# SCH_strip-table_2023-05-29.net
KiCad netlist of a schematic drawn in EasyEDA
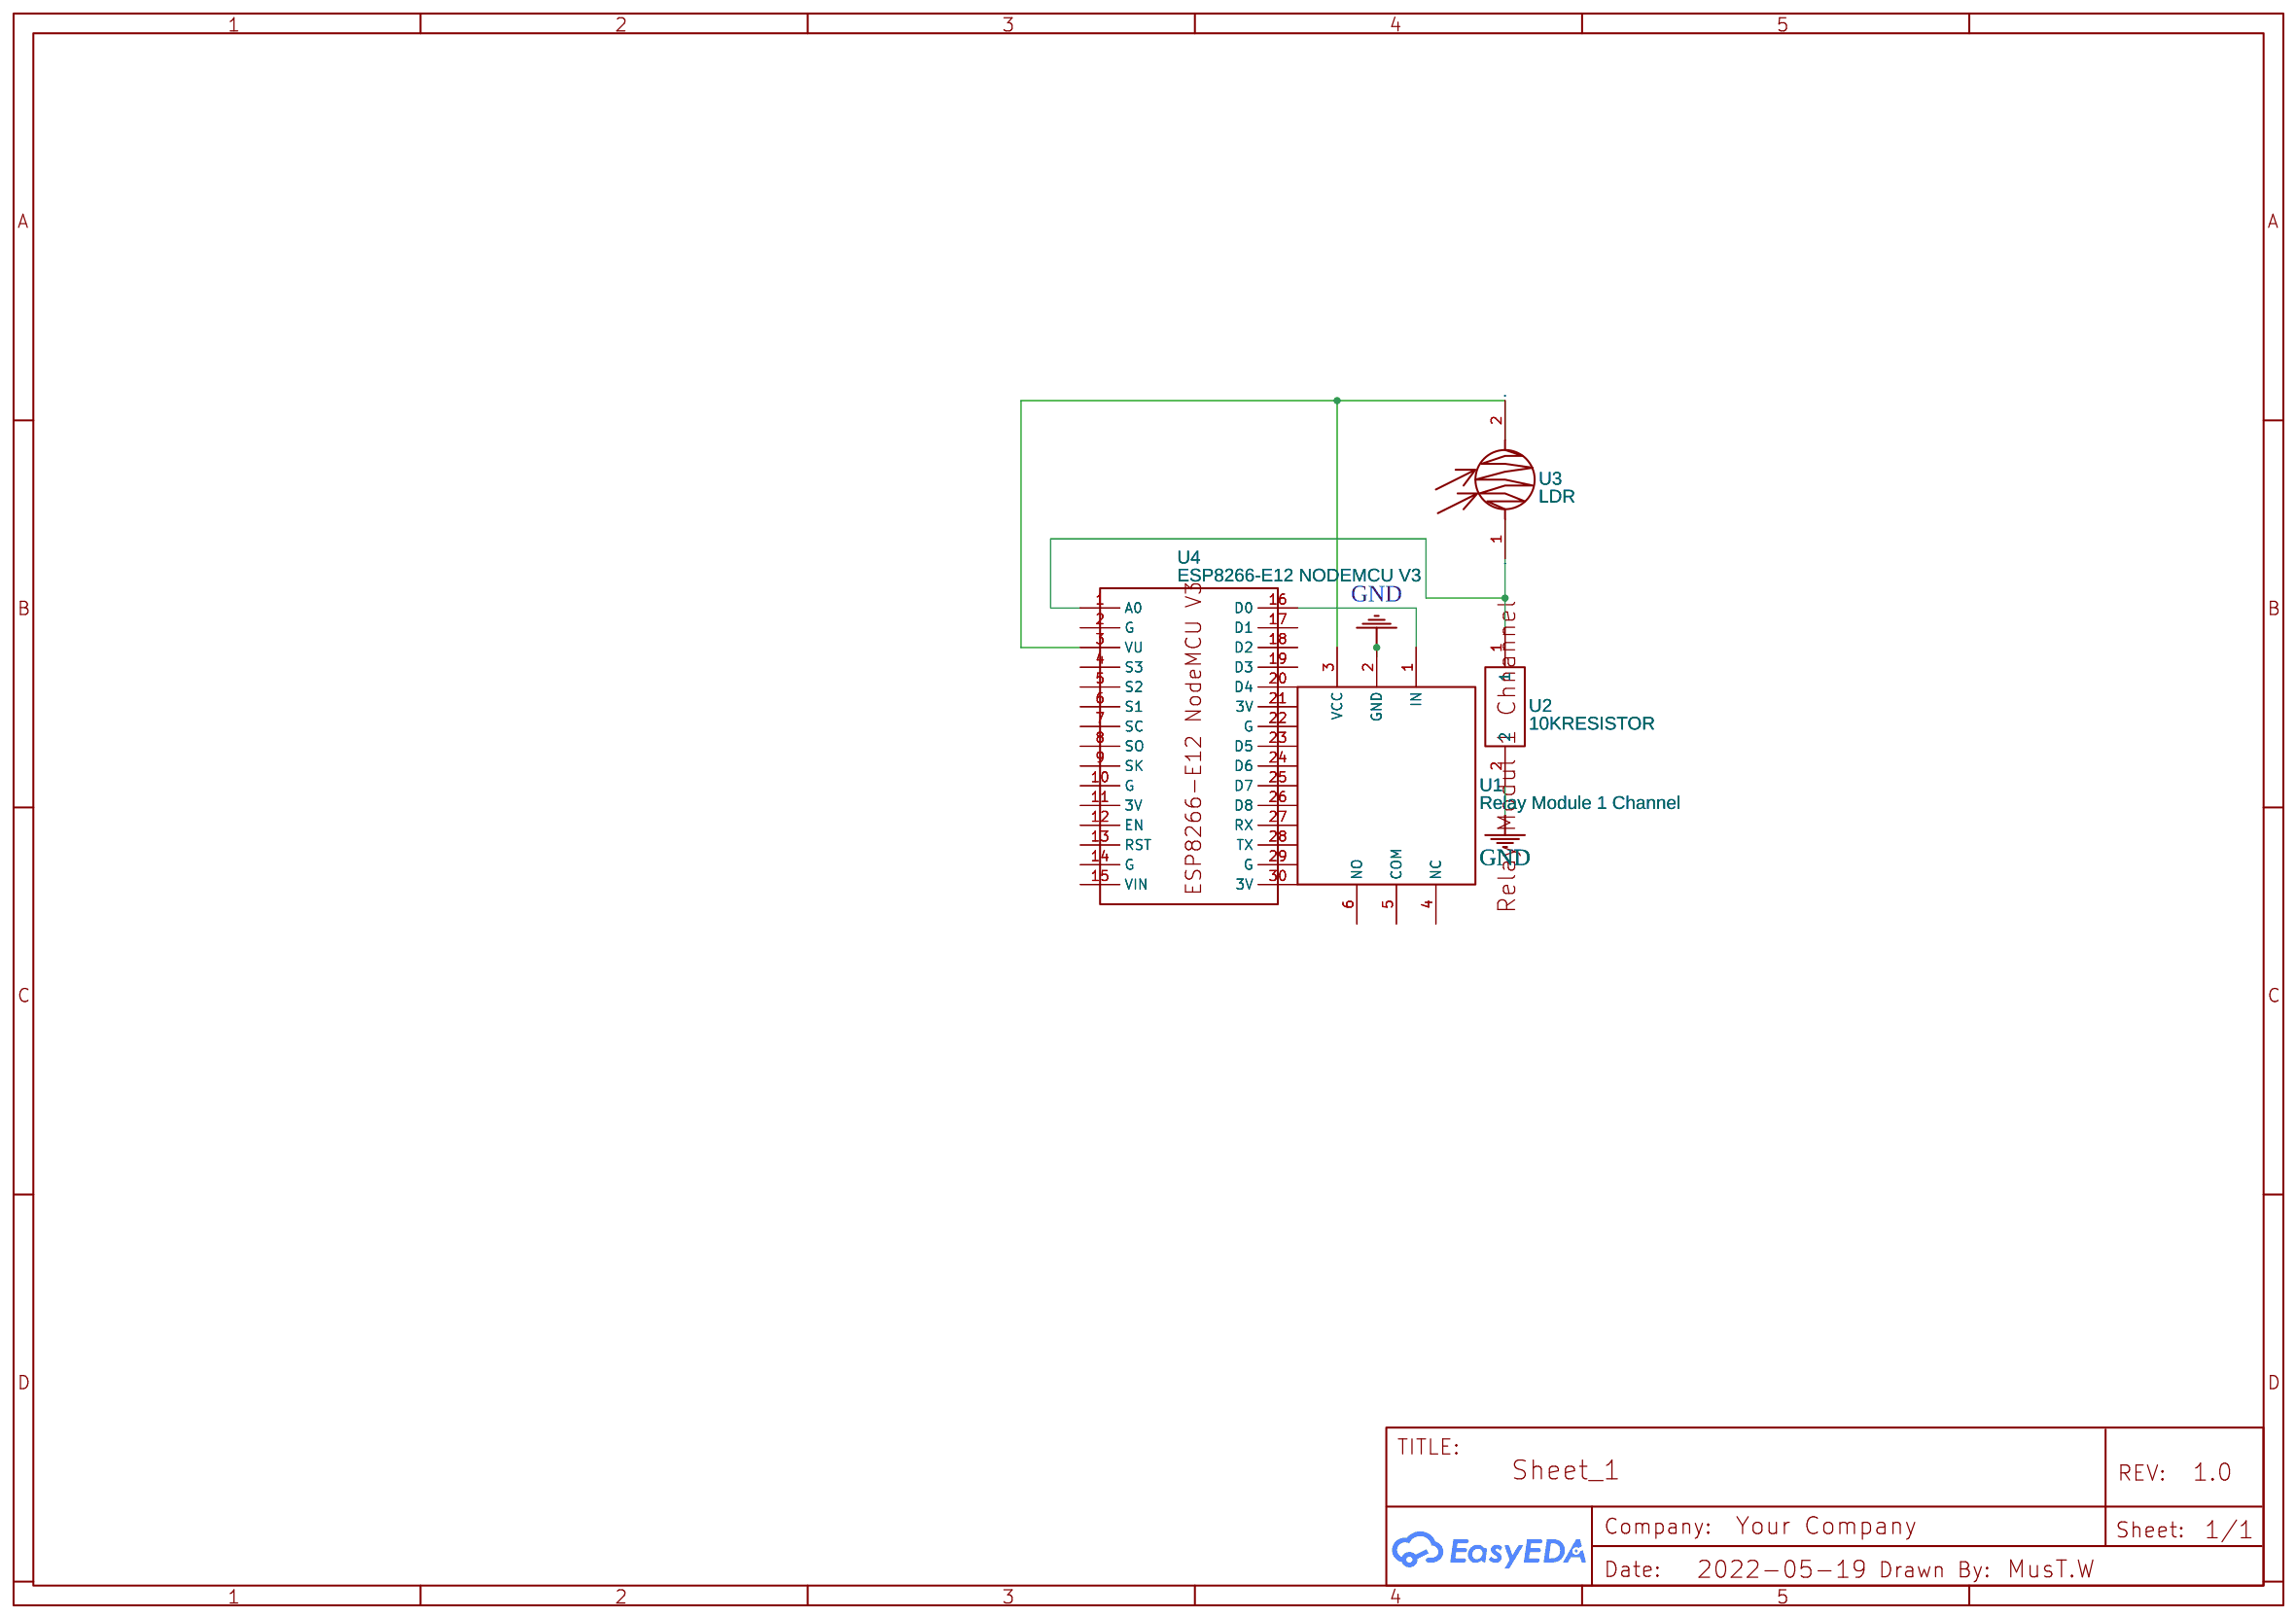
[diagram p0: schematic sheet]

(export (version "E")
  (design (tool "Eeschema 10.0.6"))
  (components
    (comp (ref "U1")
      (value "Relay Module 1 Channel")
      (fields (field (name "BOM_Manufacturer Part") "Relay Module hw-279 2 relays"))
      (libsource (lib "") (part "Relay Module 1 Channel"))
    )
    (comp (ref "U2")
      (value "10KRESISTOR")
      (fields
        (field (name "BOM_Manufacturer Part") "MCMF0W4DF1002A50")
        (field (name "BOM_Supplier Part") "1563077")
      )
      (libsource (lib "") (part "10KRESISTOR"))
    )
    (comp (ref "U3") (value "LDR") (libsource (lib "") (part "LDR")))
    (comp (ref "U4") (value "ESP8266-E12 NODEMCU V3") (libsource (lib "") (part "ESP8266-E12 NODEMCU V3")))
  )
  (nets
    (net (code "1") (name "GND") (class "Default")
      (node (ref "U1") (pin "2") (pinfunction "GND_2") (pintype "unspecified"))
      (node (ref "U2") (pin "2") (pinfunction "2_2") (pintype "unspecified"))
    )
    (net (code "2") (name "Net-(U1-IN)") (class "Default")
      (node (ref "U1") (pin "1") (pinfunction "IN_1") (pintype "unspecified"))
      (node (ref "U4") (pin "16") (pinfunction "D0_16") (pintype "unspecified"))
    )
    (net (code "3") (name "Net-(U1-VCC)") (class "Default")
      (node (ref "U1") (pin "3") (pinfunction "VCC_3") (pintype "unspecified"))
      (node (ref "U3") (pin "2") (pinfunction "2_2") (pintype "unspecified"))
      (node (ref "U4") (pin "3") (pinfunction "VU_3") (pintype "unspecified"))
    )
    (net (code "4") (name "Net-(U4-A0)") (class "Default")
      (node (ref "U2") (pin "1") (pinfunction "1_1") (pintype "unspecified"))
      (node (ref "U3") (pin "1") (pinfunction "1_1") (pintype "unspecified"))
      (node (ref "U4") (pin "1") (pinfunction "A0_1") (pintype "unspecified"))
    )
    (net (code "5") (name "unconnected-(U1-COM-Pad5)") (class "Default")
      (node (ref "U1") (pin "5") (pinfunction "COM_5") (pintype "unspecified"))
    )
    (net (code "6") (name "unconnected-(U1-NC-Pad4)") (class "Default")
      (node (ref "U1") (pin "4") (pinfunction "NC_4") (pintype "unspecified"))
    )
    (net (code "7") (name "unconnected-(U1-NO-Pad6)") (class "Default")
      (node (ref "U1") (pin "6") (pinfunction "NO_6") (pintype "unspecified"))
    )
    (net (code "8") (name "unconnected-(U4-3V-Pad11)") (class "Default")
      (node (ref "U4") (pin "11") (pinfunction "3V_11") (pintype "unspecified"))
    )
    (net (code "9") (name "unconnected-(U4-3V-Pad21)") (class "Default")
      (node (ref "U4") (pin "21") (pinfunction "3V_21") (pintype "unspecified"))
    )
    (net (code "10") (name "unconnected-(U4-3V-Pad30)") (class "Default")
      (node (ref "U4") (pin "30") (pinfunction "3V_30") (pintype "unspecified"))
    )
    (net (code "11") (name "unconnected-(U4-D1-Pad17)") (class "Default")
      (node (ref "U4") (pin "17") (pinfunction "D1_17") (pintype "unspecified"))
    )
    (net (code "12") (name "unconnected-(U4-D2-Pad18)") (class "Default")
      (node (ref "U4") (pin "18") (pinfunction "D2_18") (pintype "unspecified"))
    )
    (net (code "13") (name "unconnected-(U4-D3-Pad19)") (class "Default")
      (node (ref "U4") (pin "19") (pinfunction "D3_19") (pintype "unspecified"))
    )
    (net (code "14") (name "unconnected-(U4-D4-Pad20)") (class "Default")
      (node (ref "U4") (pin "20") (pinfunction "D4_20") (pintype "unspecified"))
    )
    (net (code "15") (name "unconnected-(U4-D5-Pad23)") (class "Default")
      (node (ref "U4") (pin "23") (pinfunction "D5_23") (pintype "unspecified"))
    )
    (net (code "16") (name "unconnected-(U4-D6-Pad24)") (class "Default")
      (node (ref "U4") (pin "24") (pinfunction "D6_24") (pintype "unspecified"))
    )
    (net (code "17") (name "unconnected-(U4-D7-Pad25)") (class "Default")
      (node (ref "U4") (pin "25") (pinfunction "D7_25") (pintype "unspecified"))
    )
    (net (code "18") (name "unconnected-(U4-D8-Pad26)") (class "Default")
      (node (ref "U4") (pin "26") (pinfunction "D8_26") (pintype "unspecified"))
    )
    (net (code "19") (name "unconnected-(U4-EN-Pad12)") (class "Default")
      (node (ref "U4") (pin "12") (pinfunction "EN_12") (pintype "unspecified"))
    )
    (net (code "20") (name "unconnected-(U4-G-Pad2)") (class "Default")
      (node (ref "U4") (pin "2") (pinfunction "G_2") (pintype "unspecified"))
    )
    (net (code "21") (name "unconnected-(U4-G-Pad10)") (class "Default")
      (node (ref "U4") (pin "10") (pinfunction "G_10") (pintype "unspecified"))
    )
    (net (code "22") (name "unconnected-(U4-G-Pad14)") (class "Default")
      (node (ref "U4") (pin "14") (pinfunction "G_14") (pintype "unspecified"))
    )
    (net (code "23") (name "unconnected-(U4-G-Pad22)") (class "Default")
      (node (ref "U4") (pin "22") (pinfunction "G_22") (pintype "unspecified"))
    )
    (net (code "24") (name "unconnected-(U4-G-Pad29)") (class "Default")
      (node (ref "U4") (pin "29") (pinfunction "G_29") (pintype "unspecified"))
    )
    (net (code "25") (name "unconnected-(U4-RST-Pad13)") (class "Default")
      (node (ref "U4") (pin "13") (pinfunction "RST_13") (pintype "unspecified"))
    )
    (net (code "26") (name "unconnected-(U4-RX-Pad27)") (class "Default")
      (node (ref "U4") (pin "27") (pinfunction "RX_27") (pintype "unspecified"))
    )
    (net (code "27") (name "unconnected-(U4-S1-Pad6)") (class "Default")
      (node (ref "U4") (pin "6") (pinfunction "S1_6") (pintype "unspecified"))
    )
    (net (code "28") (name "unconnected-(U4-S2-Pad5)") (class "Default")
      (node (ref "U4") (pin "5") (pinfunction "S2_5") (pintype "unspecified"))
    )
    (net (code "29") (name "unconnected-(U4-S3-Pad4)") (class "Default")
      (node (ref "U4") (pin "4") (pinfunction "S3_4") (pintype "unspecified"))
    )
    (net (code "30") (name "unconnected-(U4-SC-Pad7)") (class "Default")
      (node (ref "U4") (pin "7") (pinfunction "SC_7") (pintype "unspecified"))
    )
    (net (code "31") (name "unconnected-(U4-SK-Pad9)") (class "Default")
      (node (ref "U4") (pin "9") (pinfunction "SK_9") (pintype "unspecified"))
    )
    (net (code "32") (name "unconnected-(U4-SO-Pad8)") (class "Default")
      (node (ref "U4") (pin "8") (pinfunction "SO_8") (pintype "unspecified"))
    )
    (net (code "33") (name "unconnected-(U4-TX-Pad28)") (class "Default")
      (node (ref "U4") (pin "28") (pinfunction "TX_28") (pintype "unspecified"))
    )
    (net (code "34") (name "unconnected-(U4-VIN-Pad15)") (class "Default")
      (node (ref "U4") (pin "15") (pinfunction "VIN_15") (pintype "unspecified"))
    )
  )
)
